# SuperFeed.net
KiCad netlist of a schematic drawn in EAGLE
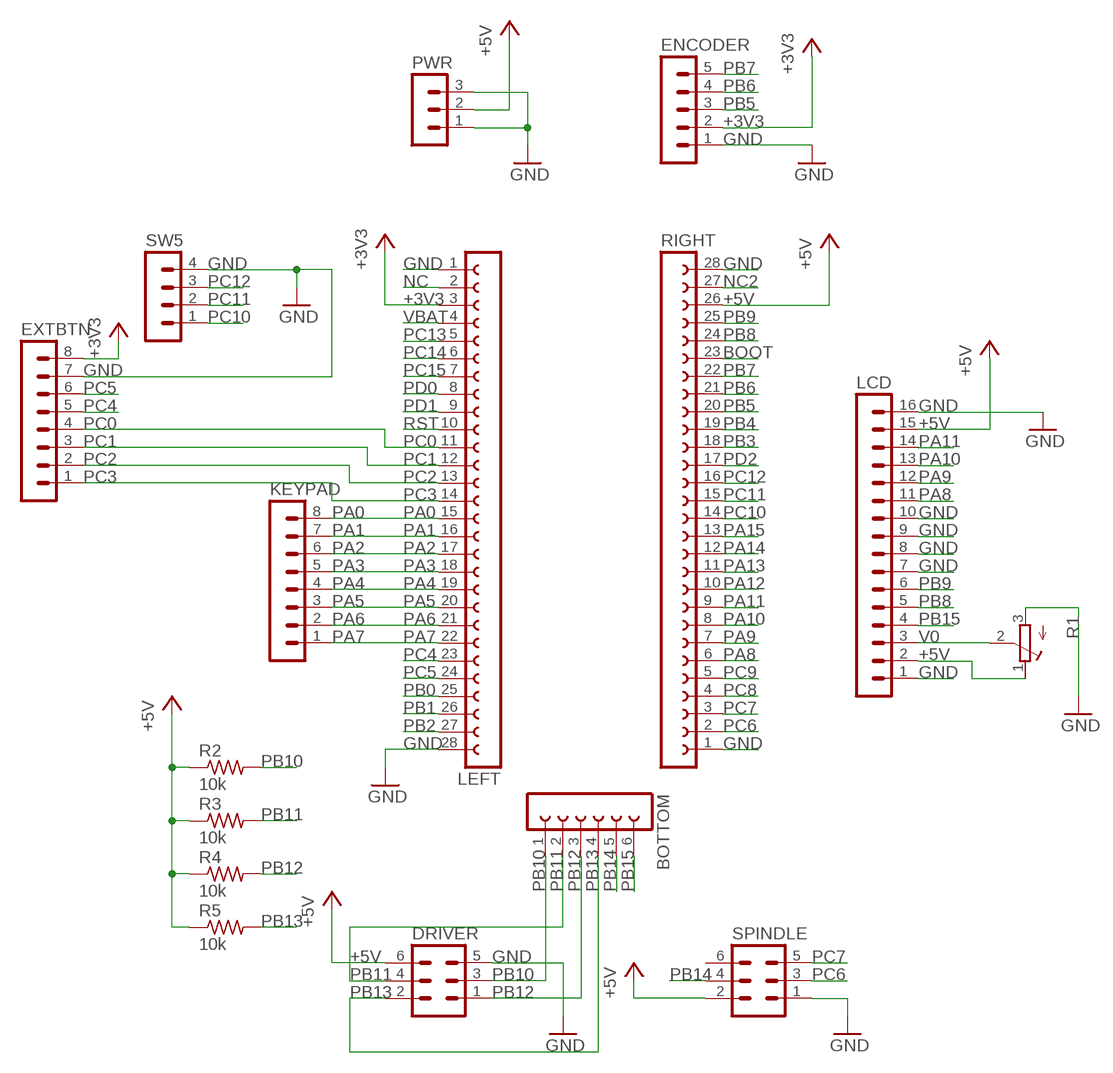
[diagram p0: schematic, sheet 1]

(export (version "E")
  (design (tool "Eeschema 10.0.6"))
  (components
    (comp (ref "BOTTOM")
      (value "FE06-1")
      (footprint "eagle-import:FE06")
      (libsource (lib "eagle-import") (part "FE06-1"))
    )
    (comp (ref "DRIVER")
      (value "MA03-2W")
      (footprint "eagle-import:MA03-2W")
      (libsource (lib "eagle-import") (part "MA03-2W"))
    )
    (comp (ref "ENCODER")
      (value "MA05-1W")
      (footprint "eagle-import:MA05-1W")
      (libsource (lib "eagle-import") (part "MA05-1W"))
    )
    (comp (ref "EXTBTN")
      (value "MA08-1W")
      (footprint "eagle-import:MA08-1W")
      (libsource (lib "eagle-import") (part "MA08-1W"))
    )
    (comp (ref "KEYPAD")
      (value "MA08-1W")
      (footprint "eagle-import:MA08-1W")
      (libsource (lib "eagle-import") (part "MA08-1W"))
    )
    (comp (ref "LCD")
      (value "MA16-1")
      (footprint "eagle-import:MA16-1")
      (libsource (lib "eagle-import") (part "MA16-1"))
    )
    (comp (ref "LEFT")
      (value "FE28-1")
      (footprint "eagle-import:FE28")
      (libsource (lib "eagle-import") (part "FE28-1"))
    )
    (comp (ref "PWR")
      (value "MA03-1W")
      (footprint "eagle-import:MA03-1W")
      (libsource (lib "eagle-import") (part "MA03-1W"))
    )
    (comp (ref "R1")
      (value "R-TRIMMT93YA")
      (footprint "eagle-import:RTRIMT93YA")
      (libsource (lib "eagle-import") (part "R-TRIMMT93YA"))
    )
    (comp (ref "R2")
      (value "10k")
      (footprint "eagle-import:0207_10")
      (libsource (lib "eagle-import") (part "R-US_0207/10"))
    )
    (comp (ref "R3")
      (value "10k")
      (footprint "eagle-import:0207_10")
      (libsource (lib "eagle-import") (part "R-US_0207/10"))
    )
    (comp (ref "R4")
      (value "10k")
      (footprint "eagle-import:0207_10")
      (libsource (lib "eagle-import") (part "R-US_0207/10"))
    )
    (comp (ref "R5")
      (value "10k")
      (footprint "eagle-import:0207_10")
      (libsource (lib "eagle-import") (part "R-US_0207/10"))
    )
    (comp (ref "RIGHT")
      (value "FE28-1")
      (footprint "eagle-import:FE28")
      (libsource (lib "eagle-import") (part "FE28-1"))
    )
    (comp (ref "SPINDLE")
      (value "MA03-2W")
      (footprint "eagle-import:MA03-2W")
      (libsource (lib "eagle-import") (part "MA03-2W"))
    )
    (comp (ref "SW5")
      (value "MA04-1W")
      (footprint "eagle-import:MA04-1W")
      (libsource (lib "eagle-import") (part "MA04-1W"))
    )
  )
  (nets
    (net (code "1") (name "+3V3") (class "Default")
      (node (ref "ENCODER") (pin "2") (pinfunction "2_2") (pintype "passive"))
      (node (ref "EXTBTN") (pin "8") (pinfunction "8_8") (pintype "passive"))
      (node (ref "LEFT") (pin "3") (pinfunction "3_3") (pintype "passive"))
    )
    (net (code "2") (name "+5V") (class "Default")
      (node (ref "DRIVER") (pin "6") (pinfunction "6_6") (pintype "passive"))
      (node (ref "LCD") (pin "15") (pinfunction "15_15") (pintype "passive"))
      (node (ref "LCD") (pin "2") (pinfunction "2_2") (pintype "passive"))
      (node (ref "PWR") (pin "2") (pinfunction "2_2") (pintype "passive"))
      (node (ref "R1") (pin "1") (pinfunction "E_1") (pintype "passive"))
      (node (ref "R2") (pin "1") (pinfunction "1_1") (pintype "passive"))
      (node (ref "R3") (pin "1") (pinfunction "1_1") (pintype "passive"))
      (node (ref "R4") (pin "1") (pinfunction "1_1") (pintype "passive"))
      (node (ref "R5") (pin "1") (pinfunction "1_1") (pintype "passive"))
      (node (ref "RIGHT") (pin "26") (pinfunction "26_26") (pintype "passive"))
      (node (ref "SPINDLE") (pin "2") (pinfunction "2_2") (pintype "passive"))
    )
    (net (code "3") (name "/BOOT") (class "Default")
      (node (ref "RIGHT") (pin "23") (pinfunction "23_23") (pintype "passive"))
    )
    (net (code "4") (name "/NC") (class "Default")
      (node (ref "LEFT") (pin "2") (pinfunction "2_2") (pintype "passive"))
    )
    (net (code "5") (name "/NC2") (class "Default")
      (node (ref "RIGHT") (pin "27") (pinfunction "27_27") (pintype "passive"))
    )
    (net (code "6") (name "/PA0") (class "Default")
      (node (ref "KEYPAD") (pin "8") (pinfunction "8_8") (pintype "passive"))
      (node (ref "LEFT") (pin "15") (pinfunction "15_15") (pintype "passive"))
    )
    (net (code "7") (name "/PA1") (class "Default")
      (node (ref "KEYPAD") (pin "7") (pinfunction "7_7") (pintype "passive"))
      (node (ref "LEFT") (pin "16") (pinfunction "16_16") (pintype "passive"))
    )
    (net (code "8") (name "/PA2") (class "Default")
      (node (ref "KEYPAD") (pin "6") (pinfunction "6_6") (pintype "passive"))
      (node (ref "LEFT") (pin "17") (pinfunction "17_17") (pintype "passive"))
    )
    (net (code "9") (name "/PA3") (class "Default")
      (node (ref "KEYPAD") (pin "5") (pinfunction "5_5") (pintype "passive"))
      (node (ref "LEFT") (pin "18") (pinfunction "18_18") (pintype "passive"))
    )
    (net (code "10") (name "/PA4") (class "Default")
      (node (ref "KEYPAD") (pin "4") (pinfunction "4_4") (pintype "passive"))
      (node (ref "LEFT") (pin "19") (pinfunction "19_19") (pintype "passive"))
    )
    (net (code "11") (name "/PA5") (class "Default")
      (node (ref "KEYPAD") (pin "3") (pinfunction "3_3") (pintype "passive"))
      (node (ref "LEFT") (pin "20") (pinfunction "20_20") (pintype "passive"))
    )
    (net (code "12") (name "/PA6") (class "Default")
      (node (ref "KEYPAD") (pin "2") (pinfunction "2_2") (pintype "passive"))
      (node (ref "LEFT") (pin "21") (pinfunction "21_21") (pintype "passive"))
    )
    (net (code "13") (name "/PA7") (class "Default")
      (node (ref "KEYPAD") (pin "1") (pinfunction "1_1") (pintype "passive"))
      (node (ref "LEFT") (pin "22") (pinfunction "22_22") (pintype "passive"))
    )
    (net (code "14") (name "/PA8") (class "Default")
      (node (ref "LCD") (pin "11") (pinfunction "11_11") (pintype "passive"))
      (node (ref "RIGHT") (pin "6") (pinfunction "6_6") (pintype "passive"))
    )
    (net (code "15") (name "/PA9") (class "Default")
      (node (ref "LCD") (pin "12") (pinfunction "12_12") (pintype "passive"))
      (node (ref "RIGHT") (pin "7") (pinfunction "7_7") (pintype "passive"))
    )
    (net (code "16") (name "/PA10") (class "Default")
      (node (ref "LCD") (pin "13") (pinfunction "13_13") (pintype "passive"))
      (node (ref "RIGHT") (pin "8") (pinfunction "8_8") (pintype "passive"))
    )
    (net (code "17") (name "/PA11") (class "Default")
      (node (ref "LCD") (pin "14") (pinfunction "14_14") (pintype "passive"))
      (node (ref "RIGHT") (pin "9") (pinfunction "9_9") (pintype "passive"))
    )
    (net (code "18") (name "/PA12") (class "Default")
      (node (ref "RIGHT") (pin "10") (pinfunction "10_10") (pintype "passive"))
    )
    (net (code "19") (name "/PA13") (class "Default")
      (node (ref "RIGHT") (pin "11") (pinfunction "11_11") (pintype "passive"))
    )
    (net (code "20") (name "/PA14") (class "Default")
      (node (ref "RIGHT") (pin "12") (pinfunction "12_12") (pintype "passive"))
    )
    (net (code "21") (name "/PA15") (class "Default")
      (node (ref "RIGHT") (pin "13") (pinfunction "13_13") (pintype "passive"))
    )
    (net (code "22") (name "/PB0") (class "Default")
      (node (ref "LEFT") (pin "25") (pinfunction "25_25") (pintype "passive"))
    )
    (net (code "23") (name "/PB1") (class "Default")
      (node (ref "LEFT") (pin "26") (pinfunction "26_26") (pintype "passive"))
    )
    (net (code "24") (name "/PB2") (class "Default")
      (node (ref "LEFT") (pin "27") (pinfunction "27_27") (pintype "passive"))
    )
    (net (code "25") (name "/PB3") (class "Default")
      (node (ref "RIGHT") (pin "18") (pinfunction "18_18") (pintype "passive"))
    )
    (net (code "26") (name "/PB4") (class "Default")
      (node (ref "RIGHT") (pin "19") (pinfunction "19_19") (pintype "passive"))
    )
    (net (code "27") (name "/PB5") (class "Default")
      (node (ref "ENCODER") (pin "3") (pinfunction "3_3") (pintype "passive"))
      (node (ref "RIGHT") (pin "20") (pinfunction "20_20") (pintype "passive"))
    )
    (net (code "28") (name "/PB6") (class "Default")
      (node (ref "ENCODER") (pin "4") (pinfunction "4_4") (pintype "passive"))
      (node (ref "RIGHT") (pin "21") (pinfunction "21_21") (pintype "passive"))
    )
    (net (code "29") (name "/PB7") (class "Default")
      (node (ref "ENCODER") (pin "5") (pinfunction "5_5") (pintype "passive"))
      (node (ref "RIGHT") (pin "22") (pinfunction "22_22") (pintype "passive"))
    )
    (net (code "30") (name "/PB8") (class "Default")
      (node (ref "LCD") (pin "5") (pinfunction "5_5") (pintype "passive"))
      (node (ref "RIGHT") (pin "24") (pinfunction "24_24") (pintype "passive"))
    )
    (net (code "31") (name "/PB9") (class "Default")
      (node (ref "LCD") (pin "6") (pinfunction "6_6") (pintype "passive"))
      (node (ref "RIGHT") (pin "25") (pinfunction "25_25") (pintype "passive"))
    )
    (net (code "32") (name "/PB10") (class "Default")
      (node (ref "BOTTOM") (pin "1") (pinfunction "1_1") (pintype "passive"))
      (node (ref "DRIVER") (pin "3") (pinfunction "3_3") (pintype "passive"))
      (node (ref "R2") (pin "2") (pinfunction "2_2") (pintype "passive"))
    )
    (net (code "33") (name "/PB11") (class "Default")
      (node (ref "BOTTOM") (pin "2") (pinfunction "2_2") (pintype "passive"))
      (node (ref "DRIVER") (pin "4") (pinfunction "4_4") (pintype "passive"))
      (node (ref "R3") (pin "2") (pinfunction "2_2") (pintype "passive"))
    )
    (net (code "34") (name "/PB12") (class "Default")
      (node (ref "BOTTOM") (pin "3") (pinfunction "3_3") (pintype "passive"))
      (node (ref "DRIVER") (pin "1") (pinfunction "1_1") (pintype "passive"))
      (node (ref "R4") (pin "2") (pinfunction "2_2") (pintype "passive"))
    )
    (net (code "35") (name "/PB13") (class "Default")
      (node (ref "BOTTOM") (pin "4") (pinfunction "4_4") (pintype "passive"))
      (node (ref "DRIVER") (pin "2") (pinfunction "2_2") (pintype "passive"))
      (node (ref "R5") (pin "2") (pinfunction "2_2") (pintype "passive"))
    )
    (net (code "36") (name "/PB14") (class "Default")
      (node (ref "BOTTOM") (pin "5") (pinfunction "5_5") (pintype "passive"))
      (node (ref "SPINDLE") (pin "4") (pinfunction "4_4") (pintype "passive"))
    )
    (net (code "37") (name "/PB15") (class "Default")
      (node (ref "BOTTOM") (pin "6") (pinfunction "6_6") (pintype "passive"))
      (node (ref "LCD") (pin "4") (pinfunction "4_4") (pintype "passive"))
    )
    (net (code "38") (name "/PC0") (class "Default")
      (node (ref "EXTBTN") (pin "4") (pinfunction "4_4") (pintype "passive"))
      (node (ref "LEFT") (pin "11") (pinfunction "11_11") (pintype "passive"))
    )
    (net (code "39") (name "/PC1") (class "Default")
      (node (ref "EXTBTN") (pin "3") (pinfunction "3_3") (pintype "passive"))
      (node (ref "LEFT") (pin "12") (pinfunction "12_12") (pintype "passive"))
    )
    (net (code "40") (name "/PC2") (class "Default")
      (node (ref "EXTBTN") (pin "2") (pinfunction "2_2") (pintype "passive"))
      (node (ref "LEFT") (pin "13") (pinfunction "13_13") (pintype "passive"))
    )
    (net (code "41") (name "/PC3") (class "Default")
      (node (ref "EXTBTN") (pin "1") (pinfunction "1_1") (pintype "passive"))
      (node (ref "LEFT") (pin "14") (pinfunction "14_14") (pintype "passive"))
    )
    (net (code "42") (name "/PC4") (class "Default")
      (node (ref "EXTBTN") (pin "5") (pinfunction "5_5") (pintype "passive"))
      (node (ref "LEFT") (pin "23") (pinfunction "23_23") (pintype "passive"))
    )
    (net (code "43") (name "/PC5") (class "Default")
      (node (ref "EXTBTN") (pin "6") (pinfunction "6_6") (pintype "passive"))
      (node (ref "LEFT") (pin "24") (pinfunction "24_24") (pintype "passive"))
    )
    (net (code "44") (name "/PC6") (class "Default")
      (node (ref "RIGHT") (pin "2") (pinfunction "2_2") (pintype "passive"))
      (node (ref "SPINDLE") (pin "3") (pinfunction "3_3") (pintype "passive"))
    )
    (net (code "45") (name "/PC7") (class "Default")
      (node (ref "RIGHT") (pin "3") (pinfunction "3_3") (pintype "passive"))
      (node (ref "SPINDLE") (pin "5") (pinfunction "5_5") (pintype "passive"))
    )
    (net (code "46") (name "/PC8") (class "Default")
      (node (ref "RIGHT") (pin "4") (pinfunction "4_4") (pintype "passive"))
    )
    (net (code "47") (name "/PC9") (class "Default")
      (node (ref "RIGHT") (pin "5") (pinfunction "5_5") (pintype "passive"))
    )
    (net (code "48") (name "/PC10") (class "Default")
      (node (ref "RIGHT") (pin "14") (pinfunction "14_14") (pintype "passive"))
      (node (ref "SW5") (pin "1") (pinfunction "1_1") (pintype "passive"))
    )
    (net (code "49") (name "/PC11") (class "Default")
      (node (ref "RIGHT") (pin "15") (pinfunction "15_15") (pintype "passive"))
      (node (ref "SW5") (pin "2") (pinfunction "2_2") (pintype "passive"))
    )
    (net (code "50") (name "/PC12") (class "Default")
      (node (ref "RIGHT") (pin "16") (pinfunction "16_16") (pintype "passive"))
      (node (ref "SW5") (pin "3") (pinfunction "3_3") (pintype "passive"))
    )
    (net (code "51") (name "/PC13") (class "Default")
      (node (ref "LEFT") (pin "5") (pinfunction "5_5") (pintype "passive"))
    )
    (net (code "52") (name "/PC14") (class "Default")
      (node (ref "LEFT") (pin "6") (pinfunction "6_6") (pintype "passive"))
    )
    (net (code "53") (name "/PC15") (class "Default")
      (node (ref "LEFT") (pin "7") (pinfunction "7_7") (pintype "passive"))
    )
    (net (code "54") (name "/PD0") (class "Default")
      (node (ref "LEFT") (pin "8") (pinfunction "8_8") (pintype "passive"))
    )
    (net (code "55") (name "/PD1") (class "Default")
      (node (ref "LEFT") (pin "9") (pinfunction "9_9") (pintype "passive"))
    )
    (net (code "56") (name "/PD2") (class "Default")
      (node (ref "RIGHT") (pin "17") (pinfunction "17_17") (pintype "passive"))
    )
    (net (code "57") (name "/RST") (class "Default")
      (node (ref "LEFT") (pin "10") (pinfunction "10_10") (pintype "passive"))
    )
    (net (code "58") (name "/V0") (class "Default")
      (node (ref "LCD") (pin "3") (pinfunction "3_3") (pintype "passive"))
      (node (ref "R1") (pin "2") (pinfunction "S_2") (pintype "passive"))
    )
    (net (code "59") (name "/VBAT") (class "Default")
      (node (ref "LEFT") (pin "4") (pinfunction "4_4") (pintype "passive"))
    )
    (net (code "60") (name "GND") (class "Default")
      (node (ref "DRIVER") (pin "5") (pinfunction "5_5") (pintype "passive"))
      (node (ref "ENCODER") (pin "1") (pinfunction "1_1") (pintype "passive"))
      (node (ref "EXTBTN") (pin "7") (pinfunction "7_7") (pintype "passive"))
      (node (ref "LCD") (pin "1") (pinfunction "1_1") (pintype "passive"))
      (node (ref "LCD") (pin "10") (pinfunction "10_10") (pintype "passive"))
      (node (ref "LCD") (pin "16") (pinfunction "16_16") (pintype "passive"))
      (node (ref "LCD") (pin "7") (pinfunction "7_7") (pintype "passive"))
      (node (ref "LCD") (pin "8") (pinfunction "8_8") (pintype "passive"))
      (node (ref "LCD") (pin "9") (pinfunction "9_9") (pintype "passive"))
      (node (ref "LEFT") (pin "1") (pinfunction "1_1") (pintype "passive"))
      (node (ref "LEFT") (pin "28") (pinfunction "28_28") (pintype "passive"))
      (node (ref "PWR") (pin "1") (pinfunction "1_1") (pintype "passive"))
      (node (ref "PWR") (pin "3") (pinfunction "3_3") (pintype "passive"))
      (node (ref "R1") (pin "3") (pinfunction "A_3") (pintype "passive"))
      (node (ref "RIGHT") (pin "1") (pinfunction "1_1") (pintype "passive"))
      (node (ref "RIGHT") (pin "28") (pinfunction "28_28") (pintype "passive"))
      (node (ref "SPINDLE") (pin "1") (pinfunction "1_1") (pintype "passive"))
      (node (ref "SW5") (pin "4") (pinfunction "4_4") (pintype "passive"))
    )
    (net (code "61") (name "unconnected-(SPINDLE-Pad6)") (class "Default")
      (node (ref "SPINDLE") (pin "6") (pinfunction "6_6") (pintype "passive"))
    )
  )
)
